# 28Pins_Schematic.net
KiCad netlist of a schematic drawn in Altium Designer
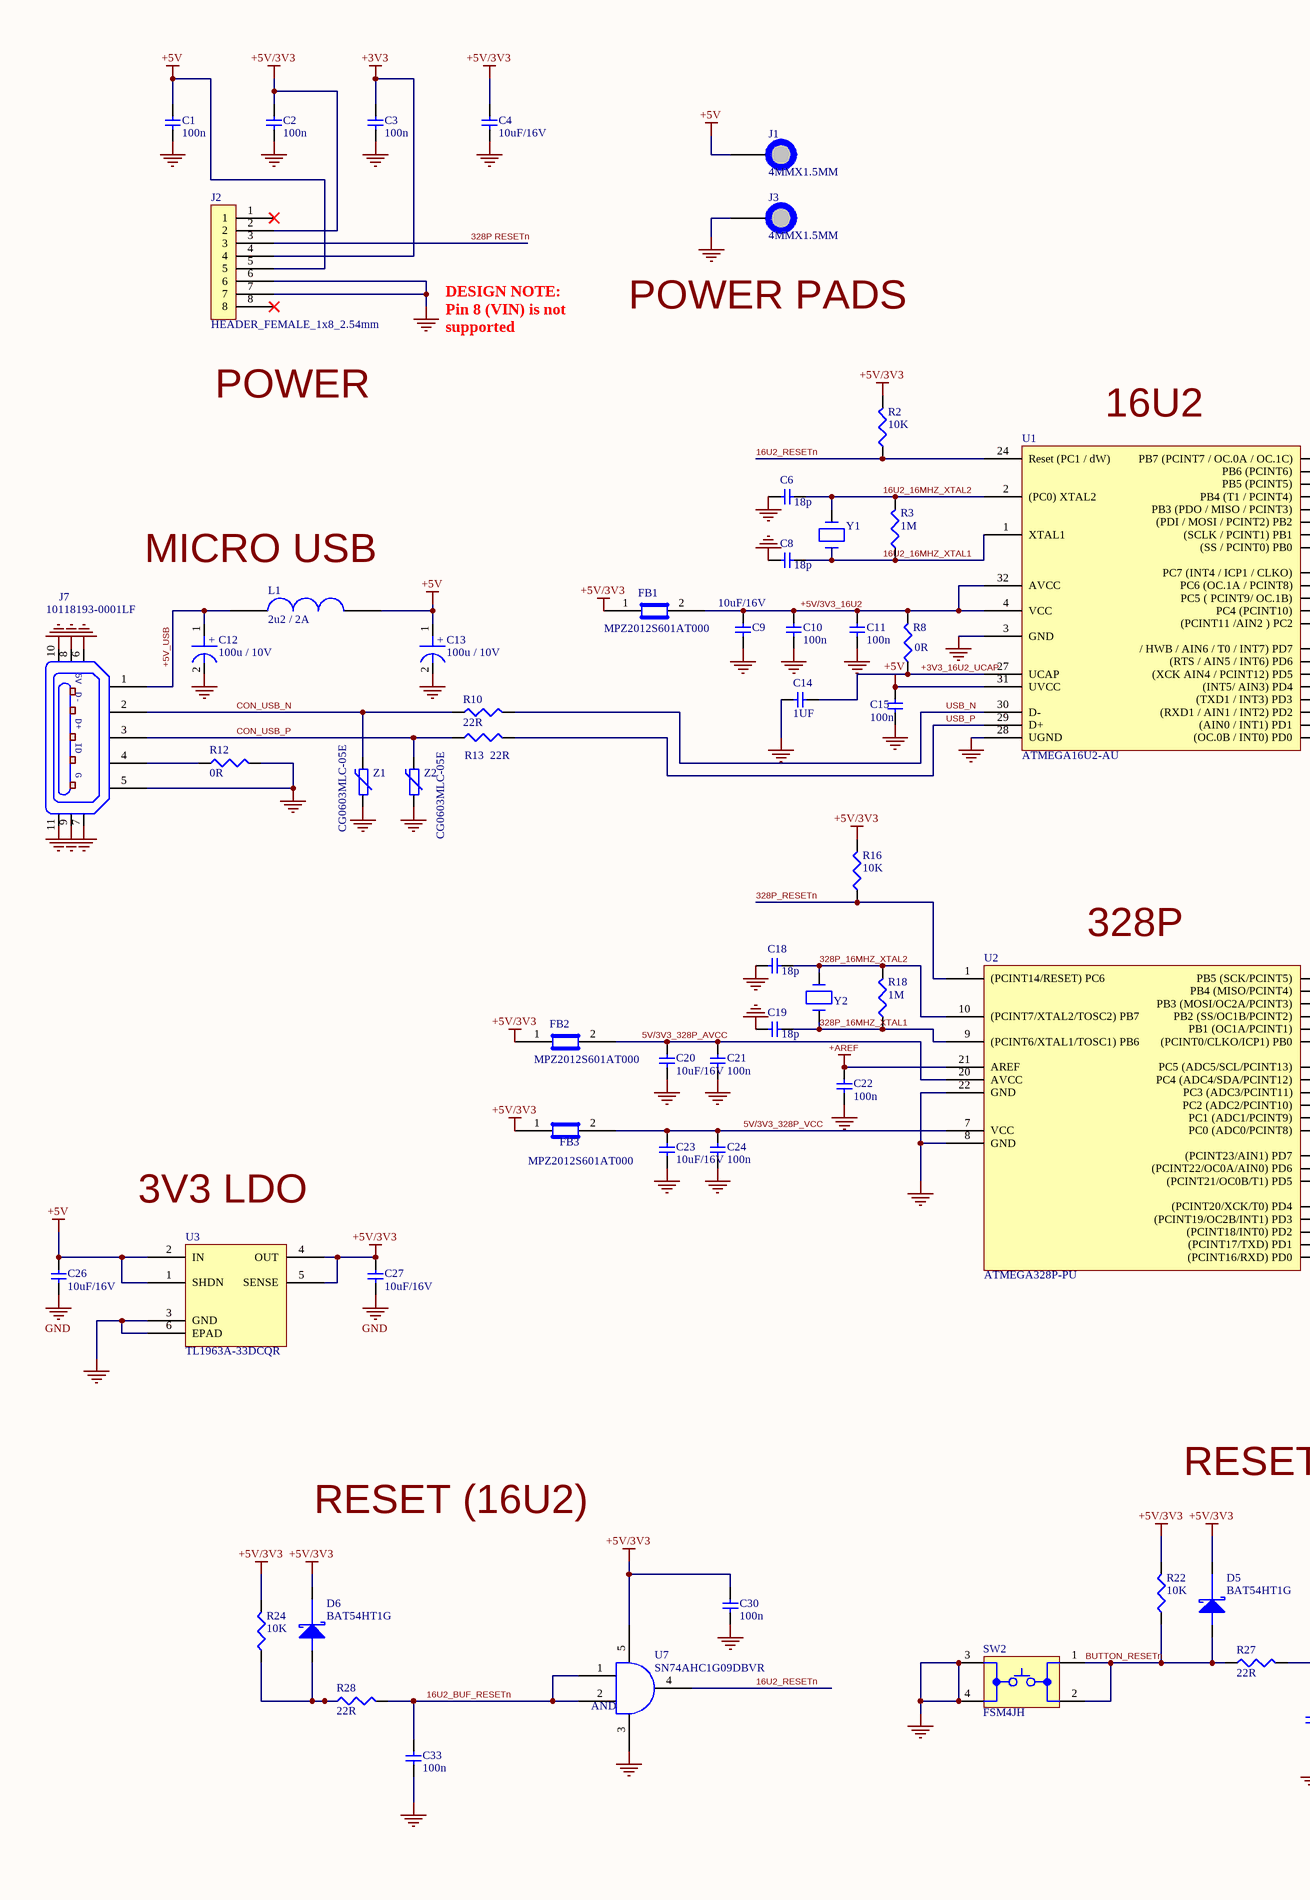
[diagram p0: 28Pins_Schematic.SchDoc, left]
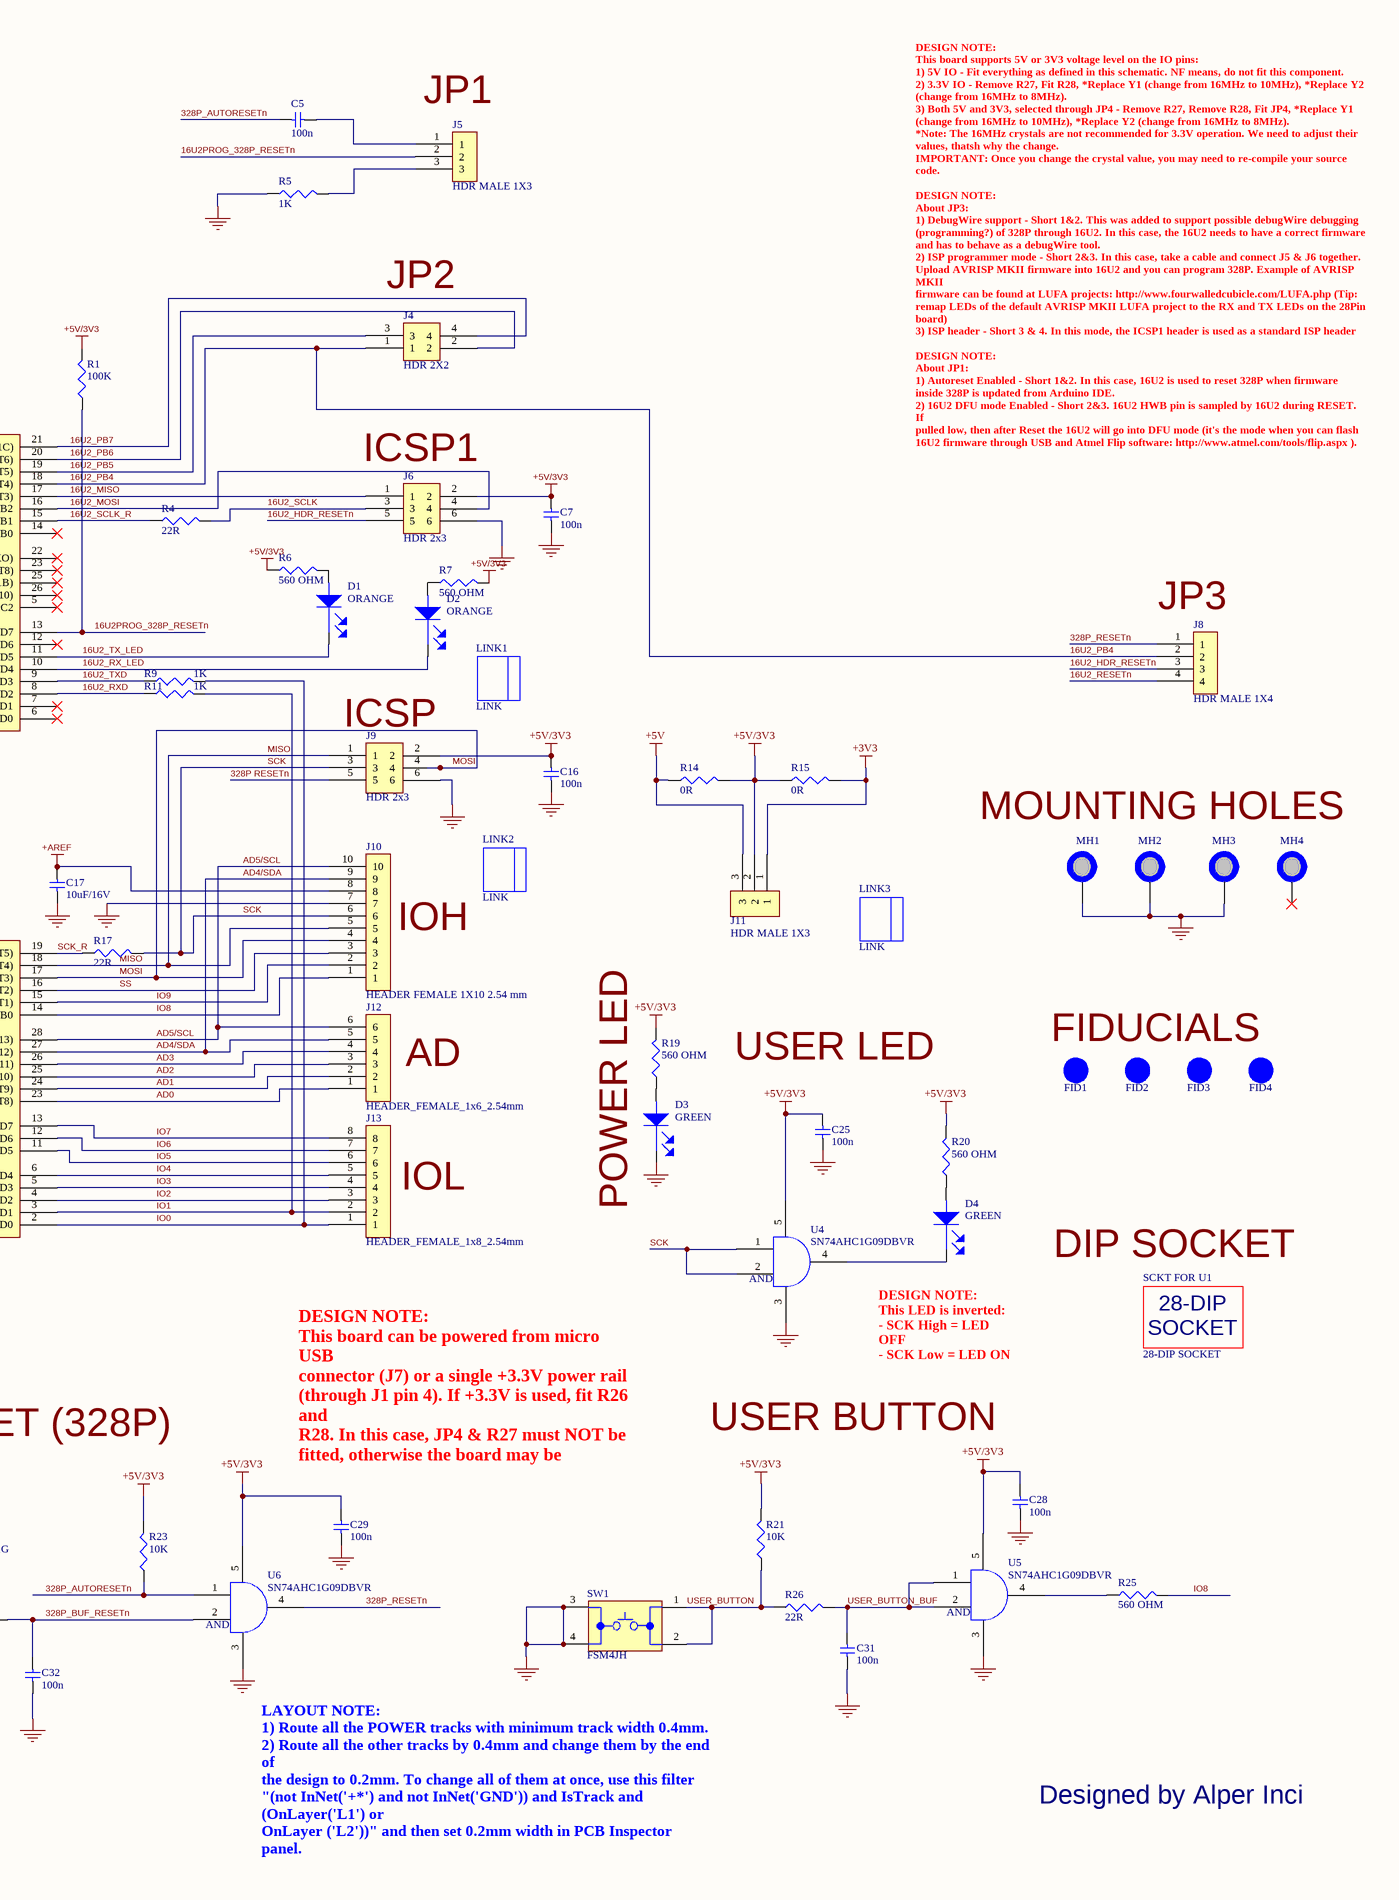
[diagram p1: 28Pins_Schematic.SchDoc, right]

(export (version "E")
  (design (tool "Eeschema 10.0.6"))
  (components
    (comp (ref "C1")
      (value "100n")
      (footprint "C0805")
      (description "CAP CER 0.1UF 50V X7R 0805")
      (fields
        (field (name "MANUFACTURER") "Mouser Electronics")
        (field (name "MANUFACTURER PART NUMBER") "C2012X7R1H104K085AA")
      )
      (libsource (lib "28_Pins_Project_V1I1") (part "C2012X7R1H104K085AA"))
    )
    (comp (ref "C2")
      (value "100n")
      (footprint "C0805")
      (description "CAP CER 0.1UF 50V X7R 0805")
      (fields
        (field (name "MANUFACTURER") "Mouser Electronics")
        (field (name "MANUFACTURER PART NUMBER") "C2012X7R1H104K085AA")
      )
      (libsource (lib "28_Pins_Project_V1I1") (part "C2012X7R1H104K085AA"))
    )
    (comp (ref "C3")
      (value "100n")
      (footprint "C0805")
      (description "CAP CER 0.1UF 50V X7R 0805")
      (fields
        (field (name "MANUFACTURER") "Mouser Electronics")
        (field (name "MANUFACTURER PART NUMBER") "C2012X7R1H104K085AA")
      )
      (libsource (lib "28_Pins_Project_V1I1") (part "C2012X7R1H104K085AA"))
    )
    (comp (ref "C4")
      (value "10uF/16V")
      (footprint "C0805_v2")
      (description "CAP CER 10UF 16V X5R 0805")
      (fields
        (field (name "MANUFACTURER") "Mouser Electronics")
        (field (name "MANUFACTURER PART NUMBER") "C2012X5R1C106M125AC")
      )
      (libsource (lib "28_Pins_Project_V1I1") (part "C2012X5R1C106M125AC"))
    )
    (comp (ref "C5")
      (value "100n")
      (footprint "C0805")
      (description "CAP CER 0.1UF 50V X7R 0805")
      (fields
        (field (name "MANUFACTURER") "Mouser Electronics")
        (field (name "MANUFACTURER PART NUMBER") "C2012X7R1H104K085AA")
      )
      (libsource (lib "28_Pins_Project_V1I1") (part "C2012X7R1H104K085AA"))
    )
    (comp (ref "C6")
      (value "18p")
      (footprint "C0805")
      (description "CAP CER 18PF 50V NP0 0805")
      (fields
        (field (name "MANUFACTURER") "KEMET")
        (field (name "MANUFACTURER PART NUMBER") "C0805C180J5GACTU")
      )
      (libsource (lib "28_Pins_Project_V1I1") (part "C0805C180J5GACTU"))
    )
    (comp (ref "C7")
      (value "100n")
      (footprint "C0805")
      (description "CAP CER 0.1UF 50V X7R 0805")
      (fields
        (field (name "MANUFACTURER") "Mouser Electronics")
        (field (name "MANUFACTURER PART NUMBER") "C2012X7R1H104K085AA")
      )
      (libsource (lib "28_Pins_Project_V1I1") (part "C2012X7R1H104K085AA"))
    )
    (comp (ref "C8")
      (value "18p")
      (footprint "C0805")
      (description "CAP CER 18PF 50V NP0 0805")
      (fields
        (field (name "MANUFACTURER") "KEMET")
        (field (name "MANUFACTURER PART NUMBER") "C0805C180J5GACTU")
      )
      (libsource (lib "28_Pins_Project_V1I1") (part "C0805C180J5GACTU"))
    )
    (comp (ref "C9")
      (value "10uF/16V")
      (footprint "C0805_v2")
      (description "CAP CER 10UF 16V X5R 0805")
      (fields
        (field (name "MANUFACTURER") "Mouser Electronics")
        (field (name "MANUFACTURER PART NUMBER") "C2012X5R1C106M125AC")
      )
      (libsource (lib "28_Pins_Project_V1I1") (part "C2012X5R1C106M125AC"))
    )
    (comp (ref "C10")
      (value "100n")
      (footprint "C0805")
      (description "CAP CER 0.1UF 50V X7R 0805")
      (fields
        (field (name "MANUFACTURER") "Mouser Electronics")
        (field (name "MANUFACTURER PART NUMBER") "C2012X7R1H104K085AA")
      )
      (libsource (lib "28_Pins_Project_V1I1") (part "C2012X7R1H104K085AA"))
    )
    (comp (ref "C11")
      (value "100n")
      (footprint "C0805")
      (description "CAP CER 0.1UF 50V X7R 0805")
      (fields
        (field (name "MANUFACTURER") "Mouser Electronics")
        (field (name "MANUFACTURER PART NUMBER") "C2012X7R1H104K085AA")
      )
      (libsource (lib "28_Pins_Project_V1I1") (part "C2012X7R1H104K085AA"))
    )
    (comp (ref "C12")
      (value "100u / 10V")
      (footprint "C_ALU_C_SIZE")
      (description "CAP ALUM 100UF 20% 10V SMD")
      (fields
        (field (name "MANUFACTURER") "Panasonic")
        (field (name "MANUFACTURER PART NUMBER") "EEE-1AA101WR")
      )
      (libsource (lib "28_Pins_Project_V1I1") (part "EEE-1AA101WR"))
    )
    (comp (ref "C13")
      (value "100u / 10V")
      (footprint "C_ALU_C_SIZE")
      (description "CAP ALUM 100UF 20% 10V SMD")
      (fields
        (field (name "MANUFACTURER") "Panasonic")
        (field (name "MANUFACTURER PART NUMBER") "EEE-1AA101WR")
      )
      (libsource (lib "28_Pins_Project_V1I1") (part "EEE-1AA101WR"))
    )
    (comp (ref "C14")
      (value "1UF")
      (footprint "C0805")
      (description "CAP CER 10UF 16V X5R 0805")
      (fields
        (field (name "MANUFACTURER") "Mouser Electronics")
        (field (name "MANUFACTURER PART NUMBER") "C2012X5R1E105K125AA")
      )
      (libsource (lib "28_Pins_Project_V1I1") (part "C2012X5R1E105K125AA"))
    )
    (comp (ref "C15")
      (value "100n")
      (footprint "C0805")
      (description "CAP CER 0.1UF 50V X7R 0805")
      (fields
        (field (name "MANUFACTURER") "Mouser Electronics")
        (field (name "MANUFACTURER PART NUMBER") "C2012X7R1H104K085AA")
      )
      (libsource (lib "28_Pins_Project_V1I1") (part "C2012X7R1H104K085AA"))
    )
    (comp (ref "C16")
      (value "100n")
      (footprint "C0805")
      (description "CAP CER 0.1UF 50V X7R 0805")
      (fields
        (field (name "MANUFACTURER") "Mouser Electronics")
        (field (name "MANUFACTURER PART NUMBER") "C2012X7R1H104K085AA")
      )
      (libsource (lib "28_Pins_Project_V1I1") (part "C2012X7R1H104K085AA"))
    )
    (comp (ref "C17")
      (value "10uF/16V")
      (footprint "C0805_v2")
      (description "CAP CER 10UF 16V X5R 0805")
      (fields
        (field (name "MANUFACTURER") "Mouser Electronics")
        (field (name "MANUFACTURER PART NUMBER") "C2012X5R1C106M125AC")
      )
      (libsource (lib "28_Pins_Project_V1I1") (part "C2012X5R1C106M125AC"))
    )
    (comp (ref "C18")
      (value "18p")
      (footprint "C0805")
      (description "CAP CER 18PF 50V NP0 0805")
      (fields
        (field (name "MANUFACTURER") "KEMET")
        (field (name "MANUFACTURER PART NUMBER") "C0805C180J5GACTU")
      )
      (libsource (lib "28_Pins_Project_V1I1") (part "C0805C180J5GACTU"))
    )
    (comp (ref "C19")
      (value "18p")
      (footprint "C0805")
      (description "CAP CER 18PF 50V NP0 0805")
      (fields
        (field (name "MANUFACTURER") "KEMET")
        (field (name "MANUFACTURER PART NUMBER") "C0805C180J5GACTU")
      )
      (libsource (lib "28_Pins_Project_V1I1") (part "C0805C180J5GACTU"))
    )
    (comp (ref "C20")
      (value "10uF/16V")
      (footprint "C0805_v2")
      (description "CAP CER 10UF 16V X5R 0805")
      (fields
        (field (name "MANUFACTURER") "Mouser Electronics")
        (field (name "MANUFACTURER PART NUMBER") "C2012X5R1C106M125AC")
      )
      (libsource (lib "28_Pins_Project_V1I1") (part "C2012X5R1C106M125AC"))
    )
    (comp (ref "C21")
      (value "100n")
      (footprint "C0805")
      (description "CAP CER 0.1UF 50V X7R 0805")
      (fields
        (field (name "MANUFACTURER") "Mouser Electronics")
        (field (name "MANUFACTURER PART NUMBER") "C2012X7R1H104K085AA")
      )
      (libsource (lib "28_Pins_Project_V1I1") (part "C2012X7R1H104K085AA"))
    )
    (comp (ref "C22")
      (value "100n")
      (footprint "C0805")
      (description "CAP CER 0.1UF 50V X7R 0805")
      (fields
        (field (name "MANUFACTURER") "Mouser Electronics")
        (field (name "MANUFACTURER PART NUMBER") "C2012X7R1H104K085AA")
      )
      (libsource (lib "28_Pins_Project_V1I1") (part "C2012X7R1H104K085AA"))
    )
    (comp (ref "C23")
      (value "10uF/16V")
      (footprint "C0805_v2")
      (description "CAP CER 10UF 16V X5R 0805")
      (fields
        (field (name "MANUFACTURER") "Mouser Electronics")
        (field (name "MANUFACTURER PART NUMBER") "C2012X5R1C106M125AC")
      )
      (libsource (lib "28_Pins_Project_V1I1") (part "C2012X5R1C106M125AC"))
    )
    (comp (ref "C24")
      (value "100n")
      (footprint "C0805")
      (description "CAP CER 0.1UF 50V X7R 0805")
      (fields
        (field (name "MANUFACTURER") "Mouser Electronics")
        (field (name "MANUFACTURER PART NUMBER") "C2012X7R1H104K085AA")
      )
      (libsource (lib "28_Pins_Project_V1I1") (part "C2012X7R1H104K085AA"))
    )
    (comp (ref "C25")
      (value "100n")
      (footprint "C0805")
      (description "CAP CER 0.1UF 50V X7R 0805")
      (fields
        (field (name "MANUFACTURER") "Mouser Electronics")
        (field (name "MANUFACTURER PART NUMBER") "C2012X7R1H104K085AA")
      )
      (libsource (lib "28_Pins_Project_V1I1") (part "C2012X7R1H104K085AA"))
    )
    (comp (ref "C26")
      (value "10uF/16V")
      (footprint "C0805_v2")
      (description "CAP CER 10UF 16V X5R 0805")
      (fields
        (field (name "MANUFACTURER") "Mouser Electronics")
        (field (name "MANUFACTURER PART NUMBER") "C2012X5R1C106M125AC")
      )
      (libsource (lib "28_Pins_Project_V1I1") (part "C2012X5R1C106M125AC"))
    )
    (comp (ref "C27")
      (value "10uF/16V")
      (footprint "C0805_v2")
      (description "CAP CER 10UF 16V X5R 0805")
      (fields
        (field (name "MANUFACTURER") "Mouser Electronics")
        (field (name "MANUFACTURER PART NUMBER") "C2012X5R1C106M125AC")
      )
      (libsource (lib "28_Pins_Project_V1I1") (part "C2012X5R1C106M125AC"))
    )
    (comp (ref "C28")
      (value "100n")
      (footprint "C0805")
      (description "CAP CER 0.1UF 50V X7R 0805")
      (fields
        (field (name "MANUFACTURER") "Mouser Electronics")
        (field (name "MANUFACTURER PART NUMBER") "C2012X7R1H104K085AA")
      )
      (libsource (lib "28_Pins_Project_V1I1") (part "C2012X7R1H104K085AA"))
    )
    (comp (ref "C29")
      (value "100n")
      (footprint "C0805")
      (description "CAP CER 0.1UF 50V X7R 0805")
      (fields
        (field (name "MANUFACTURER") "Mouser Electronics")
        (field (name "MANUFACTURER PART NUMBER") "C2012X7R1H104K085AA")
      )
      (libsource (lib "28_Pins_Project_V1I1") (part "C2012X7R1H104K085AA"))
    )
    (comp (ref "C30")
      (value "100n")
      (footprint "C0805")
      (description "CAP CER 0.1UF 50V X7R 0805")
      (fields
        (field (name "MANUFACTURER") "Mouser Electronics")
        (field (name "MANUFACTURER PART NUMBER") "C2012X7R1H104K085AA")
      )
      (libsource (lib "28_Pins_Project_V1I1") (part "C2012X7R1H104K085AA"))
    )
    (comp (ref "C31")
      (value "100n")
      (footprint "C0805")
      (description "CAP CER 0.1UF 50V X7R 0805")
      (fields
        (field (name "MANUFACTURER") "Mouser Electronics")
        (field (name "MANUFACTURER PART NUMBER") "C2012X7R1H104K085AA")
      )
      (libsource (lib "28_Pins_Project_V1I1") (part "C2012X7R1H104K085AA"))
    )
    (comp (ref "C32")
      (value "100n")
      (footprint "C0805")
      (description "CAP CER 0.1UF 50V X7R 0805")
      (fields
        (field (name "MANUFACTURER") "Mouser Electronics")
        (field (name "MANUFACTURER PART NUMBER") "C2012X7R1H104K085AA")
      )
      (libsource (lib "28_Pins_Project_V1I1") (part "C2012X7R1H104K085AA"))
    )
    (comp (ref "C33")
      (value "100n")
      (footprint "C0805")
      (description "CAP CER 0.1UF 50V X7R 0805")
      (fields
        (field (name "MANUFACTURER") "Mouser Electronics")
        (field (name "MANUFACTURER PART NUMBER") "C2012X7R1H104K085AA")
      )
      (libsource (lib "28_Pins_Project_V1I1") (part "C2012X7R1H104K085AA"))
    )
    (comp (ref "D1")
      (value "ORANGE")
      (footprint "LED_0603")
      (description "LED ORANGE DIFFUSED 0603 SMD")
      (fields
        (field (name "MANUFACTURER") "Carling Technologies")
        (field (name "MANUFACTURER PART NUMBER") "LO L29K-H2K1-24-Z")
      )
      (libsource (lib "28_Pins_Project_V1I1") (part "LO L29K-H2K1-24-Z"))
    )
    (comp (ref "D2")
      (value "ORANGE")
      (footprint "LED_0603")
      (description "LED ORANGE DIFFUSED 0603 SMD")
      (fields
        (field (name "MANUFACTURER") "Carling Technologies")
        (field (name "MANUFACTURER PART NUMBER") "LO L29K-H2K1-24-Z")
      )
      (libsource (lib "28_Pins_Project_V1I1") (part "LO L29K-H2K1-24-Z"))
    )
    (comp (ref "D3")
      (value "GREEN")
      (footprint "LED_0603")
      (description "LED GREEN DIFFUSED 0603 SMD")
      (fields
        (field (name "MANUFACTURER") "Osram Opto Semiconductors")
        (field (name "MANUFACTURER PART NUMBER") "LG L29K-G2J1-24-Z")
      )
      (libsource (lib "28_Pins_Project_V1I1") (part "LG L29K-G2J1-24-Z"))
    )
    (comp (ref "D4")
      (value "GREEN")
      (footprint "LED_0603")
      (description "LED GREEN DIFFUSED 0603 SMD")
      (fields
        (field (name "MANUFACTURER") "Osram Opto Semiconductors")
        (field (name "MANUFACTURER PART NUMBER") "LG L29K-G2J1-24-Z")
      )
      (libsource (lib "28_Pins_Project_V1I1") (part "LG L29K-G2J1-24-Z"))
    )
    (comp (ref "D5")
      (value "BAT54HT1G")
      (footprint "SOD323")
      (description "DIODE SCHOTTKY 30V 200MA SOD323")
      (fields (field (name "MANUFACTURER") "ON Semiconductor"))
      (libsource (lib "28_Pins_Project_V1I1") (part "BAT54HT1G"))
    )
    (comp (ref "D6")
      (value "BAT54HT1G")
      (footprint "SOD323")
      (description "DIODE SCHOTTKY 30V 200MA SOD323")
      (fields (field (name "MANUFACTURER") "ON Semiconductor"))
      (libsource (lib "28_Pins_Project_V1I1") (part "BAT54HT1G"))
    )
    (comp (ref "FB1")
      (value "MPZ2012S601AT000")
      (footprint "C0805")
      (description "FERRITE CHIP BEAD  600 OHM SMD")
      (fields (field (name "MANUFACTURER") "Mouser Electronics"))
      (libsource (lib "28_Pins_Project_V1I1") (part "MPZ2012S601AT000"))
    )
    (comp (ref "FB2")
      (value "MPZ2012S601AT000")
      (footprint "C0805")
      (description "FERRITE CHIP BEAD  600 OHM SMD")
      (fields (field (name "MANUFACTURER") "Mouser Electronics"))
      (libsource (lib "28_Pins_Project_V1I1") (part "MPZ2012S601AT000"))
    )
    (comp (ref "FB3")
      (value "MPZ2012S601AT000")
      (footprint "C0805")
      (description "FERRITE CHIP BEAD  600 OHM SMD")
      (fields (field (name "MANUFACTURER") "Mouser Electronics"))
      (libsource (lib "28_Pins_Project_V1I1") (part "MPZ2012S601AT000"))
    )
    (comp (ref "FID1")
      (value "FID 1MM")
      (footprint "FID_40X120D")
      (description "FIDUCIAL 40MIL DIAMETER,120 MIL MASK")
      (libsource (lib "28_Pins_Project_V1I1") (part "FID_1MMC"))
    )
    (comp (ref "FID2")
      (value "FID 1MM")
      (footprint "FID_40X120D")
      (description "FIDUCIAL 40MIL DIAMETER,120 MIL MASK")
      (libsource (lib "28_Pins_Project_V1I1") (part "FID_1MMC"))
    )
    (comp (ref "FID3")
      (value "FID 1MM")
      (footprint "FID_40X120D")
      (description "FIDUCIAL 40MIL DIAMETER,120 MIL MASK")
      (libsource (lib "28_Pins_Project_V1I1") (part "FID_1MMC"))
    )
    (comp (ref "FID4")
      (value "FID 1MM")
      (footprint "FID_40X120D")
      (description "FIDUCIAL 40MIL DIAMETER,120 MIL MASK")
      (libsource (lib "28_Pins_Project_V1I1") (part "FID_1MMC"))
    )
    (comp (ref "J1")
      (value "4MMX1.5MM")
      (footprint "PAD_WTIH_HOLE_4MMX1.5MM")
      (description "PAD WITH A HOLE")
      (libsource (lib "28_Pins_Project_V1I1") (part "PAD_WITH_HOLE_4MMX1.5MM"))
    )
    (comp (ref "J2")
      (value "HEADER_FEMALE_1x8_2.54mm")
      (footprint "HEADER_FEMALE_1X8_2.54mm")
      (description "HARWIN 2.54mm 8 Way 1 Row Straight PCBSocket Through Hole Socket Strip")
      (fields
        (field (name "MANUFACTURER") "Mouser Electronics")
        (field (name "MANUFACTURER PART NUMBER") "M20-7820842")
      )
      (libsource (lib "28_Pins_Project_V1I1") (part "M20-7820842"))
    )
    (comp (ref "J3")
      (value "4MMX1.5MM")
      (footprint "PAD_WTIH_HOLE_4MMX1.5MM")
      (description "PAD WITH A HOLE")
      (libsource (lib "28_Pins_Project_V1I1") (part "PAD_WITH_HOLE_4MMX1.5MM"))
    )
    (comp (ref "J4")
      (value "HDR 2X2")
      (footprint "HDR_2X2_2.54mm")
      (description "CONN HEADER 4POS .100 STR 30AU")
      (fields
        (field (name "MANUFACTURER") "Mouser Electronics")
        (field (name "MANUFACTURER PART NUMBER") "68602-204HLF")
      )
      (libsource (lib "28_Pins_Project_V1I1") (part "68602-204HLF"))
    )
    (comp (ref "J5")
      (value "HDR MALE 1X3")
      (footprint "HEADER_MALE_1X3_2.54mm")
      (description "HDR MALE 1X3 2.54 MM")
      (fields
        (field (name "MANUFACTURER") "Amphenol ICC")
        (field (name "MANUFACTURER PART NUMBER") "68000-103HLF")
      )
      (libsource (lib "") (part "68000-103HLF_1"))
    )
    (comp (ref "J6")
      (value "HDR 2x3")
      (footprint "HDR_2X3_2.54mm")
      (description "CONN HEADER 6POS .100 STR 30AU")
      (fields
        (field (name "MANUFACTURER") "Amphenol ICC")
        (field (name "MANUFACTURER PART NUMBER") "67997-106HLF")
      )
      (libsource (lib "28_Pins_Project_V1I1") (part "67997-106HLF"))
    )
    (comp (ref "J7")
      (value "10118193-0001LF")
      (footprint "10118193")
      (description "CONN USB MICRO B RECPT SMT R/A")
      (fields (field (name "MANUFACTURER") "Amphenol ICC"))
      (libsource (lib "28_Pins_Project_V1I1") (part "10118193-0001LF"))
    )
    (comp (ref "J8")
      (value "HDR MALE 1X4")
      (footprint "HEADER_MALE_1X4_2.54mm")
      (description "HDR MALE 1X4 2.54MM")
      (fields
        (field (name "MANUFACTURER") "Amphenol ICC")
        (field (name "MANUFACTURER PART NUMBER") "68001-204HLF")
      )
      (libsource (lib "28_Pins_Project_V1I1") (part "68001-204HLF"))
    )
    (comp (ref "J9")
      (value "HDR 2x3")
      (footprint "HDR_2X3_2.54mm")
      (description "CONN HEADER 6POS .100 STR 30AU")
      (fields
        (field (name "MANUFACTURER") "Amphenol ICC")
        (field (name "MANUFACTURER PART NUMBER") "67997-106HLF")
      )
      (libsource (lib "28_Pins_Project_V1I1") (part "67997-106HLF"))
    )
    (comp (ref "J10")
      (value "HEADER FEMALE 1X10 2.54 mm")
      (footprint "HEADER_FEMALE_1X10_2.54mm")
      (description "HARWIN 2.54mm 10 Way 1 Row Straight PCBSocket Through Hole Socket Strip")
      (fields (field (name "MANUFACTURER PART NUMBER") "M20-7821046"))
      (libsource (lib "28_Pins_Project_V1I1") (part "M20-7821046"))
    )
    (comp (ref "J11")
      (value "HDR MALE 1X3")
      (footprint "HEADER_MALE_1X3_2.54mm")
      (description "HDR MALE 1X3 2.54 MM")
      (fields
        (field (name "MANUFACTURER") "Amphenol ICC")
        (field (name "MANUFACTURER PART NUMBER") "68000-103HLF")
      )
      (libsource (lib "28_Pins_Project_V1I1") (part "68000-103HLF"))
    )
    (comp (ref "J12")
      (value "HEADER_FEMALE_1x6_2.54mm")
      (footprint "HEADER_FEMALE_1X6_2.54mm")
      (description "HARWIN 2.54mm 6 Way 1 Row Straight PCBSocket Through Hole Socket Strip")
      (fields
        (field (name "MANUFACTURER") "Mouser Electronics")
        (field (name "MANUFACTURER PART NUMBER") "M20-7820646")
      )
      (libsource (lib "28_Pins_Project_V1I1") (part "M20-7820646"))
    )
    (comp (ref "J13")
      (value "HEADER_FEMALE_1x8_2.54mm")
      (footprint "HEADER_FEMALE_1X8_2.54mm")
      (description "HARWIN 2.54mm 8 Way 1 Row Straight PCBSocket Through Hole Socket Strip")
      (fields
        (field (name "MANUFACTURER") "Mouser Electronics")
        (field (name "MANUFACTURER PART NUMBER") "M20-7820842")
      )
      (libsource (lib "") (part "M20-7820842_1"))
    )
    (comp (ref "L1")
      (value "2u2 / 2A")
      (footprint "C1210_IND")
      (description "FIXED IND 2.2UH 2A 80MOHM SMD")
      (fields
        (field (name "MANUFACTURER") "Mouser Electronics")
        (field (name "MANUFACTURER PART NUMBER") "L1210R2R2MDWIT")
      )
      (libsource (lib "28_Pins_Project_V1I1") (part "L1210R2R2MDWIT"))
    )
    (comp (ref "LINK1")
      (value "LINK")
      (description "QPC02SXGN-RC")
      (fields (field (name "MANUFACTURER") "Mouser Electronics"))
      (libsource (lib "28_Pins_Project_V1I1") (part "QPC02SXGN-RC"))
    )
    (comp (ref "LINK2")
      (value "LINK")
      (description "QPC02SXGN-RC")
      (fields (field (name "MANUFACTURER") "Mouser Electronics"))
      (libsource (lib "28_Pins_Project_V1I1") (part "QPC02SXGN-RC"))
    )
    (comp (ref "LINK3")
      (value "LINK")
      (description "QPC02SXGN-RC")
      (fields (field (name "MANUFACTURER") "Mouser Electronics"))
      (libsource (lib "28_Pins_Project_V1I1") (part "QPC02SXGN-RC"))
    )
    (comp (ref "MH1")
      (value "MH_7.4MMC_3.2MMD")
      (footprint "MH_7.4MMC_3.2MMD")
      (description "MOUNTING HOLE 7.4MM DIAMETER,3.2MM DRILL")
      (libsource (lib "28_Pins_Project_V1I1") (part "MH_7.4MMC_3.2MMD"))
    )
    (comp (ref "MH2")
      (value "MH_7.4MMC_3.2MMD")
      (footprint "MH_7.4MMC_3.2MMD")
      (description "MOUNTING HOLE 7.4MM DIAMETER,3.2MM DRILL")
      (libsource (lib "28_Pins_Project_V1I1") (part "MH_7.4MMC_3.2MMD"))
    )
    (comp (ref "MH3")
      (value "MH_7.4MMC_3.2MMD")
      (footprint "MH_7.4MMC_3.2MMD")
      (description "MOUNTING HOLE 7.4MM DIAMETER,3.2MM DRILL")
      (libsource (lib "28_Pins_Project_V1I1") (part "MH_7.4MMC_3.2MMD"))
    )
    (comp (ref "MH4")
      (value "MH_7.4MMNC_3.2MMD")
      (footprint "MH_7.4MMNC_3.2MMD_NON_COPPER_NPTH")
      (description "HOLE 7.4MM DIAMETER (NON COPPER), 3.2MM DRILL NPTH")
      (libsource (lib "28_Pins_Project_V1I1") (part "MH_7.4MMNC_3.2MMD"))
    )
    (comp (ref "R1")
      (value "100K")
      (footprint "R0805")
      (description "RES SMD 100K OHM 1% 1/8W 0805")
      (fields
        (field (name "MANUFACTURER") "Mouser Electronics")
        (field (name "MANUFACTURER PART NUMBER") "RC0805FR-07100KL")
      )
      (libsource (lib "28_Pins_Project_V1I1") (part "RC0805FR-07100KL"))
    )
    (comp (ref "R2")
      (value "10K")
      (footprint "R0805")
      (description "RES SMD 10K OHM 1/8 W 0805")
      (fields
        (field (name "MANUFACTURER") "Mouser Electronics")
        (field (name "MANUFACTURER PART NUMBER") "RC0805FR-0710KL")
      )
      (libsource (lib "28_Pins_Project_V1I1") (part "RC0805FR-0710KL"))
    )
    (comp (ref "R3")
      (value "1M")
      (footprint "R0805")
      (description "RES SMD 1M OHM 1% 1/8W 0805")
      (fields
        (field (name "MANUFACTURER") "Mouser Electronics")
        (field (name "MANUFACTURER PART NUMBER") "RC0805FR-071ML")
      )
      (libsource (lib "28_Pins_Project_V1I1") (part "RC0805FR-071ML"))
    )
    (comp (ref "R4")
      (value "22R")
      (footprint "R0805")
      (description "RES SMD 22 OHM 1% 1/8W 0805")
      (fields
        (field (name "MANUFACTURER") "Mouser Electronics")
        (field (name "MANUFACTURER PART NUMBER") "RC0805FR-0722RL")
      )
      (libsource (lib "28_Pins_Project_V1I1") (part "RC0805FR-0722RL"))
    )
    (comp (ref "R5")
      (value "1K")
      (footprint "R0805")
      (description "RES SMD 1K OHM 1% 1/8W 0805")
      (fields
        (field (name "MANUFACTURER") "Mouser Electronics")
        (field (name "MANUFACTURER PART NUMBER") "RC0805FR-071KL")
      )
      (libsource (lib "28_Pins_Project_V1I1") (part "RC0805FR-071KL"))
    )
    (comp (ref "R6")
      (value "560 OHM")
      (footprint "R0805")
      (description "RES SMD 560 OHM 1% 1/8W 0805")
      (fields
        (field (name "MANUFACTURER") "Mouser Electronics")
        (field (name "MANUFACTURER PART NUMBER") "RC0805FR-07560RL")
      )
      (libsource (lib "28_Pins_Project_V1I1") (part "RC0805FR-07560RL"))
    )
    (comp (ref "R7")
      (value "560 OHM")
      (footprint "R0805")
      (description "RES SMD 560 OHM 1% 1/8W 0805")
      (fields
        (field (name "MANUFACTURER") "Mouser Electronics")
        (field (name "MANUFACTURER PART NUMBER") "RC0805FR-07560RL")
      )
      (libsource (lib "28_Pins_Project_V1I1") (part "RC0805FR-07560RL"))
    )
    (comp (ref "R8")
      (value "0R")
      (footprint "R0805")
      (description "RES SMD 0 OHM 1% 1/8W 0805")
      (fields
        (field (name "MANUFACTURER") "Mouser Electronics")
        (field (name "MANUFACTURER PART NUMBER") "RC0805JR-070RL")
      )
      (libsource (lib "28_Pins_Project_V1I1") (part "RC0805JR-070RL"))
    )
    (comp (ref "R9")
      (value "1K")
      (footprint "R0805")
      (description "RES SMD 1K OHM 1% 1/8W 0805")
      (fields
        (field (name "MANUFACTURER") "Mouser Electronics")
        (field (name "MANUFACTURER PART NUMBER") "RC0805FR-071KL")
      )
      (libsource (lib "28_Pins_Project_V1I1") (part "RC0805FR-071KL"))
    )
    (comp (ref "R10")
      (value "22R")
      (footprint "R0805")
      (description "RES SMD 22 OHM 1% 1/8W 0805")
      (fields
        (field (name "MANUFACTURER") "Mouser Electronics")
        (field (name "MANUFACTURER PART NUMBER") "RC0805FR-0722RL")
      )
      (libsource (lib "28_Pins_Project_V1I1") (part "RC0805FR-0722RL"))
    )
    (comp (ref "R11")
      (value "1K")
      (footprint "R0805")
      (description "RES SMD 1K OHM 1% 1/8W 0805")
      (fields
        (field (name "MANUFACTURER") "Mouser Electronics")
        (field (name "MANUFACTURER PART NUMBER") "RC0805FR-071KL")
      )
      (libsource (lib "28_Pins_Project_V1I1") (part "RC0805FR-071KL"))
    )
    (comp (ref "R12")
      (value "0R")
      (footprint "R0805")
      (description "RES SMD 0 OHM 1% 1/8W 0805")
      (fields
        (field (name "MANUFACTURER") "Mouser Electronics")
        (field (name "MANUFACTURER PART NUMBER") "RC0805JR-070RL")
      )
      (libsource (lib "28_Pins_Project_V1I1") (part "RC0805JR-070RL"))
    )
    (comp (ref "R13")
      (value "22R")
      (footprint "R0805")
      (description "RES SMD 22 OHM 1% 1/8W 0805")
      (fields
        (field (name "MANUFACTURER") "Mouser Electronics")
        (field (name "MANUFACTURER PART NUMBER") "RC0805FR-0722RL")
      )
      (libsource (lib "28_Pins_Project_V1I1") (part "RC0805FR-0722RL"))
    )
    (comp (ref "R14")
      (value "0R")
      (footprint "R0805")
      (description "RES SMD 0 OHM 1% 1/8W 0805")
      (fields
        (field (name "MANUFACTURER") "Mouser Electronics")
        (field (name "MANUFACTURER PART NUMBER") "RC0805JR-070RL")
      )
      (libsource (lib "") (part "RC0805JR-070RL_1"))
    )
    (comp (ref "R15")
      (value "0R")
      (footprint "R0805")
      (description "RES SMD 0 OHM 1% 1/8W 0805")
      (fields
        (field (name "MANUFACTURER") "Mouser Electronics")
        (field (name "MANUFACTURER PART NUMBER") "RC0805JR-070RL")
      )
      (libsource (lib "") (part "RC0805JR-070RL_1"))
    )
    (comp (ref "R16")
      (value "10K")
      (footprint "R0805")
      (description "RES SMD 10K OHM 1/8 W 0805")
      (fields
        (field (name "MANUFACTURER") "Mouser Electronics")
        (field (name "MANUFACTURER PART NUMBER") "RC0805FR-0710KL")
      )
      (libsource (lib "28_Pins_Project_V1I1") (part "RC0805FR-0710KL"))
    )
    (comp (ref "R17")
      (value "22R")
      (footprint "R0805")
      (description "RES SMD 22 OHM 1% 1/8W 0805")
      (fields
        (field (name "MANUFACTURER") "Mouser Electronics")
        (field (name "MANUFACTURER PART NUMBER") "RC0805FR-0722RL")
      )
      (libsource (lib "28_Pins_Project_V1I1") (part "RC0805FR-0722RL"))
    )
    (comp (ref "R18")
      (value "1M")
      (footprint "R0805")
      (description "RES SMD 1M OHM 1% 1/8W 0805")
      (fields
        (field (name "MANUFACTURER") "Mouser Electronics")
        (field (name "MANUFACTURER PART NUMBER") "RC0805FR-071ML")
      )
      (libsource (lib "28_Pins_Project_V1I1") (part "RC0805FR-071ML"))
    )
    (comp (ref "R19")
      (value "560 OHM")
      (footprint "R0805")
      (description "RES SMD 560 OHM 1% 1/8W 0805")
      (fields
        (field (name "MANUFACTURER") "Mouser Electronics")
        (field (name "MANUFACTURER PART NUMBER") "RC0805FR-07560RL")
      )
      (libsource (lib "28_Pins_Project_V1I1") (part "RC0805FR-07560RL"))
    )
    (comp (ref "R20")
      (value "560 OHM")
      (footprint "R0805")
      (description "RES SMD 560 OHM 1% 1/8W 0805")
      (fields
        (field (name "MANUFACTURER") "Mouser Electronics")
        (field (name "MANUFACTURER PART NUMBER") "RC0805FR-07560RL")
      )
      (libsource (lib "28_Pins_Project_V1I1") (part "RC0805FR-07560RL"))
    )
    (comp (ref "R21")
      (value "10K")
      (footprint "R0805")
      (description "RES SMD 10K OHM 1/8 W 0805")
      (fields
        (field (name "MANUFACTURER") "Mouser Electronics")
        (field (name "MANUFACTURER PART NUMBER") "RC0805FR-0710KL")
      )
      (libsource (lib "28_Pins_Project_V1I1") (part "RC0805FR-0710KL"))
    )
    (comp (ref "R22")
      (value "10K")
      (footprint "R0805")
      (description "RES SMD 10K OHM 1/8 W 0805")
      (fields
        (field (name "MANUFACTURER") "Mouser Electronics")
        (field (name "MANUFACTURER PART NUMBER") "RC0805FR-0710KL")
      )
      (libsource (lib "28_Pins_Project_V1I1") (part "RC0805FR-0710KL"))
    )
    (comp (ref "R23")
      (value "10K")
      (footprint "R0805")
      (description "RES SMD 10K OHM 1/8 W 0805")
      (fields
        (field (name "MANUFACTURER") "Mouser Electronics")
        (field (name "MANUFACTURER PART NUMBER") "RC0805FR-0710KL")
      )
      (libsource (lib "28_Pins_Project_V1I1") (part "RC0805FR-0710KL"))
    )
    (comp (ref "R24")
      (value "10K")
      (footprint "R0805")
      (description "RES SMD 10K OHM 1/8 W 0805")
      (fields
        (field (name "MANUFACTURER") "Mouser Electronics")
        (field (name "MANUFACTURER PART NUMBER") "RC0805FR-0710KL")
      )
      (libsource (lib "28_Pins_Project_V1I1") (part "RC0805FR-0710KL"))
    )
    (comp (ref "R25")
      (value "560 OHM")
      (footprint "R0805")
      (description "RES SMD 560 OHM 1% 1/8W 0805")
      (fields
        (field (name "MANUFACTURER") "Mouser Electronics")
        (field (name "MANUFACTURER PART NUMBER") "RC0805FR-07560RL")
      )
      (libsource (lib "28_Pins_Project_V1I1") (part "RC0805FR-07560RL"))
    )
    (comp (ref "R26")
      (value "22R")
      (footprint "R0805")
      (description "RES SMD 22 OHM 1% 1/8W 0805")
      (fields
        (field (name "MANUFACTURER") "Mouser Electronics")
        (field (name "MANUFACTURER PART NUMBER") "RC0805FR-0722RL")
      )
      (libsource (lib "28_Pins_Project_V1I1") (part "RC0805FR-0722RL"))
    )
    (comp (ref "R27")
      (value "22R")
      (footprint "R0805")
      (description "RES SMD 22 OHM 1% 1/8W 0805")
      (fields
        (field (name "MANUFACTURER") "Mouser Electronics")
        (field (name "MANUFACTURER PART NUMBER") "RC0805FR-0722RL")
      )
      (libsource (lib "28_Pins_Project_V1I1") (part "RC0805FR-0722RL"))
    )
    (comp (ref "R28")
      (value "22R")
      (footprint "R0805")
      (description "RES SMD 22 OHM 1% 1/8W 0805")
      (fields
        (field (name "MANUFACTURER") "Mouser Electronics")
        (field (name "MANUFACTURER PART NUMBER") "RC0805FR-0722RL")
      )
      (libsource (lib "28_Pins_Project_V1I1") (part "RC0805FR-0722RL"))
    )
    (comp (ref "SCKT FOR U1")
      (value "28-DIP SOCKET")
      (footprint "28_DIP_7.62MM_SOCKET")
      (description "CONN IC  DIP SOCKET 28POS TIN")
      (fields (field (name "MANUFACTURER") "3M") (field (name "MANUFACTURER PART NUMBER") "4828-3004-CP"))
      (libsource (lib "28_Pins_Project_V1I1") (part "4828-3004-CP"))
    )
    (comp (ref "SW1")
      (value "FSM4JH")
      (footprint "FSM4JH")
      (description "Alcoswitch, Switch,Pushbutton,Tactile,SPST,50mA,Thru Hole,6mm")
      (fields (field (name "MANUFACTURER") "TE Connectivity"))
      (libsource (lib "28_Pins_Project_V1I1") (part "FSM4JH"))
    )
    (comp (ref "SW2")
      (value "FSM4JH")
      (footprint "FSM4JH")
      (description "Alcoswitch, Switch,Pushbutton,Tactile,SPST,50mA,Thru Hole,6mm")
      (fields (field (name "MANUFACTURER") "TE Connectivity"))
      (libsource (lib "28_Pins_Project_V1I1") (part "FSM4JH"))
    )
    (comp (ref "U1")
      (value "ATMEGA16U2-AU")
      (footprint "TQFP32")
      (fields (field (name "MANUFACTURER") "Mouser Electronics"))
      (libsource (lib "28_Pins_Project_V1I1") (part "ATMEGA16U2-AU"))
    )
    (comp (ref "U2")
      (value "ATMEGA328P-PU")
      (footprint "28_DIP_7.62mm")
      (description "ATMEGA328P-PU; 8 bit Microcontroller AVR 20MHz 1; 32kb Flash; 2kb RAM; I2C SPI 2")
      (fields (field (name "MANUFACTURER") "Microchip Technology Inc."))
      (libsource (lib "28_Pins_Project_V1I1") (part "ATMEGA328P-PU"))
    )
    (comp (ref "U3")
      (value "TL1963A-33DCQR")
      (footprint "DCQ (R-PDSO-G6)")
      (description "IC REG LDO 3.3V 1.5A SOT223-6")
      (fields (field (name "MANUFACTURER") "Mouser Electronics"))
      (libsource (lib "28_Pins_Project_V1I1") (part "TL1963A-33DCQR"))
    )
    (comp (ref "U4")
      (value "SN74AHC1G09DBVR")
      (footprint "DBV_SOT_23_5")
      (description "IC GATE AND 1 CH 2-INP SOT-23-5")
      (fields (field (name "MANUFACTURER") "Mouser Electronics"))
      (libsource (lib "28_Pins_Project_V1I1") (part "SN74AHC1G09DBVR"))
    )
    (comp (ref "U5")
      (value "SN74AHC1G09DBVR")
      (footprint "DBV_SOT_23_5")
      (description "IC GATE AND 1 CH 2-INP SOT-23-5")
      (fields (field (name "MANUFACTURER") "Mouser Electronics"))
      (libsource (lib "28_Pins_Project_V1I1") (part "SN74AHC1G09DBVR"))
    )
    (comp (ref "U6")
      (value "SN74AHC1G09DBVR")
      (footprint "DBV_SOT_23_5")
      (description "IC GATE AND 1 CH 2-INP SOT-23-5")
      (fields (field (name "MANUFACTURER") "Mouser Electronics"))
      (libsource (lib "28_Pins_Project_V1I1") (part "SN74AHC1G09DBVR"))
    )
    (comp (ref "U7")
      (value "SN74AHC1G09DBVR")
      (footprint "DBV_SOT_23_5")
      (description "IC GATE AND 1 CH 2-INP SOT-23-5")
      (fields (field (name "MANUFACTURER") "Mouser Electronics"))
      (libsource (lib "28_Pins_Project_V1I1") (part "SN74AHC1G09DBVR"))
    )
    (comp (ref "Y1")
      (value "ABM7-16.000MHZ-D2Y-T")
      (footprint "ABM_v1_1_BIG")
      (description "Crystal; Ceramic; 16.000MHZ; 18pf; 20ppm @ 25C; 30ppm -40+85C; 6.0 x 3.5 x 1.2mm; T/R")
      (fields (field (name "MANUFACTURER") "Abracon"))
      (libsource (lib "28_Pins_Project_V1I1") (part "ABM7-16.000MHZ-D2Y-T"))
    )
    (comp (ref "Y2")
      (value "ABM7-16.000MHZ-D2Y-T")
      (footprint "ABM_v1_1_BIG")
      (description "Crystal; Ceramic; 16.000MHZ; 18pf; 20ppm @ 25C; 30ppm -40+85C; 6.0 x 3.5 x 1.2mm; T/R")
      (fields (field (name "MANUFACTURER") "Abracon"))
      (libsource (lib "28_Pins_Project_V1I1") (part "ABM7-16.000MHZ-D2Y-T"))
    )
    (comp (ref "Z1")
      (value "CG0603MLC-05E")
      (footprint "R0603")
      (description "VARISTOR 0603")
      (fields (field (name "MANUFACTURER") "Bourns"))
      (libsource (lib "28_Pins_Project_V1I1") (part "CG0603MLC-05E"))
    )
    (comp (ref "Z2")
      (value "CG0603MLC-05E")
      (footprint "R0603")
      (description "VARISTOR 0603")
      (fields (field (name "MANUFACTURER") "Bourns"))
      (libsource (lib "28_Pins_Project_V1I1") (part "CG0603MLC-05E"))
    )
  )
  (nets
    (net (code "1") (name "+3V3") (class "Default")
      (node (ref "C3") (pin "2") (pinfunction "2_2") (pintype "passive"))
      (node (ref "J11") (pin "1") (pinfunction "1_1") (pintype "passive"))
      (node (ref "J2") (pin "4") (pinfunction "4_4") (pintype "passive"))
      (node (ref "R15") (pin "2") (pinfunction "1_2") (pintype "passive"))
    )
    (net (code "2") (name "+5V") (class "Default")
      (node (ref "C1") (pin "2") (pinfunction "2_2") (pintype "passive"))
      (node (ref "C13") (pin "1") (pinfunction "1_1") (pintype "passive"))
      (node (ref "C15") (pin "2") (pinfunction "2_2") (pintype "passive"))
      (node (ref "C26") (pin "2") (pinfunction "2_2") (pintype "passive"))
      (node (ref "J1") (pin "1") (pinfunction "1_1") (pintype "passive"))
      (node (ref "J11") (pin "3") (pinfunction "3_3") (pintype "passive"))
      (node (ref "J2") (pin "5") (pinfunction "5_5") (pintype "passive"))
      (node (ref "L1") (pin "4") (pinfunction "4_4") (pintype "passive"))
      (node (ref "U1") (pin "31") (pinfunction "UVCC_31") (pintype "passive"))
      (node (ref "U3") (pin "1") (pinfunction "SHDN_1") (pintype "passive"))
      (node (ref "U3") (pin "2") (pinfunction "IN_2") (pintype "passive"))
    )
    (net (code "3") (name "+5V{slash}3V3") (class "Default")
      (node (ref "C16") (pin "2") (pinfunction "2_2") (pintype "passive"))
      (node (ref "C2") (pin "2") (pinfunction "2_2") (pintype "passive"))
      (node (ref "C25") (pin "2") (pinfunction "2_2") (pintype "passive"))
      (node (ref "C27") (pin "2") (pinfunction "2_2") (pintype "passive"))
      (node (ref "C28") (pin "2") (pinfunction "2_2") (pintype "passive"))
      (node (ref "C29") (pin "2") (pinfunction "2_2") (pintype "passive"))
      (node (ref "C30") (pin "2") (pinfunction "2_2") (pintype "passive"))
      (node (ref "C4") (pin "2") (pinfunction "2_2") (pintype "passive"))
      (node (ref "C7") (pin "2") (pinfunction "2_2") (pintype "passive"))
      (node (ref "D5") (pin "1") (pinfunction "Cathode_1") (pintype "passive"))
      (node (ref "D6") (pin "1") (pinfunction "Cathode_1") (pintype "passive"))
      (node (ref "FB1") (pin "1") (pinfunction "1_1") (pintype "passive"))
      (node (ref "FB2") (pin "1") (pinfunction "1_1") (pintype "passive"))
      (node (ref "FB3") (pin "1") (pinfunction "1_1") (pintype "passive"))
      (node (ref "J11") (pin "2") (pinfunction "2_2") (pintype "passive"))
      (node (ref "J2") (pin "2") (pinfunction "2_2") (pintype "passive"))
      (node (ref "J6") (pin "2") (pinfunction "2_2") (pintype "passive"))
      (node (ref "J9") (pin "2") (pinfunction "2_2") (pintype "passive"))
      (node (ref "R1") (pin "2") (pinfunction "1_2") (pintype "passive"))
      (node (ref "R14") (pin "2") (pinfunction "1_2") (pintype "passive"))
      (node (ref "R16") (pin "2") (pinfunction "1_2") (pintype "passive"))
      (node (ref "R19") (pin "2") (pinfunction "1_2") (pintype "passive"))
      (node (ref "R2") (pin "2") (pinfunction "1_2") (pintype "passive"))
      (node (ref "R20") (pin "2") (pinfunction "1_2") (pintype "passive"))
      (node (ref "R21") (pin "2") (pinfunction "1_2") (pintype "passive"))
      (node (ref "R22") (pin "2") (pinfunction "1_2") (pintype "passive"))
      (node (ref "R23") (pin "2") (pinfunction "1_2") (pintype "passive"))
      (node (ref "R24") (pin "2") (pinfunction "1_2") (pintype "passive"))
      (node (ref "R6") (pin "1") (pinfunction "1_1") (pintype "passive"))
      (node (ref "R7") (pin "2") (pinfunction "1_2") (pintype "passive"))
      (node (ref "U3") (pin "4") (pinfunction "OUT_4") (pintype "passive"))
      (node (ref "U3") (pin "5") (pinfunction "SENSE_5") (pintype "passive"))
      (node (ref "U4") (pin "5") (pinfunction "5_5") (pintype "passive"))
      (node (ref "U5") (pin "5") (pinfunction "5_5") (pintype "passive"))
      (node (ref "U6") (pin "5") (pinfunction "5_5") (pintype "passive"))
      (node (ref "U7") (pin "5") (pinfunction "5_5") (pintype "passive"))
    )
    (net (code "4") (name "+AREF") (class "Default")
      (node (ref "C17") (pin "2") (pinfunction "2_2") (pintype "passive"))
      (node (ref "C22") (pin "2") (pinfunction "2_2") (pintype "passive"))
      (node (ref "J10") (pin "8") (pinfunction "8_8") (pintype "passive"))
      (node (ref "U2") (pin "21") (pinfunction "AREF_21") (pintype "passive"))
    )
    (net (code "5") (name "/+3V3_16U2_UCAP") (class "Default")
      (node (ref "C14") (pin "2") (pinfunction "2_2") (pintype "passive"))
      (node (ref "R8") (pin "2") (pinfunction "1_2") (pintype "passive"))
      (node (ref "U1") (pin "27") (pinfunction "UCAP_27") (pintype "passive"))
    )
    (net (code "6") (name "/+5V_USB") (class "Default")
      (node (ref "C12") (pin "1") (pinfunction "1_1") (pintype "passive"))
      (node (ref "J7") (pin "1") (pinfunction "1_1") (pintype "passive"))
      (node (ref "L1") (pin "3") (pinfunction "3_3") (pintype "passive"))
    )
    (net (code "7") (name "/+5V{slash}3V3_16U2") (class "Default")
      (node (ref "C10") (pin "2") (pinfunction "2_2") (pintype "passive"))
      (node (ref "C11") (pin "2") (pinfunction "2_2") (pintype "passive"))
      (node (ref "C9") (pin "2") (pinfunction "2_2") (pintype "passive"))
      (node (ref "FB1") (pin "2") (pinfunction "2_2") (pintype "passive"))
      (node (ref "R8") (pin "2") (pinfunction "1_2") (pintype "passive"))
      (node (ref "U1") (pin "32") (pinfunction "AVCC_32") (pintype "passive"))
      (node (ref "U1") (pin "4") (pinfunction "VCC_4") (pintype "passive"))
    )
    (net (code "8") (name "/5V{slash}3V3_328P_AVCC") (class "Default")
      (node (ref "C20") (pin "2") (pinfunction "2_2") (pintype "passive"))
      (node (ref "C21") (pin "2") (pinfunction "2_2") (pintype "passive"))
      (node (ref "FB2") (pin "2") (pinfunction "2_2") (pintype "passive"))
      (node (ref "U2") (pin "20") (pinfunction "AVCC_20") (pintype "passive"))
    )
    (net (code "9") (name "/5V{slash}3V3_328P_VCC") (class "Default")
      (node (ref "C23") (pin "2") (pinfunction "2_2") (pintype "passive"))
      (node (ref "C24") (pin "2") (pinfunction "2_2") (pintype "passive"))
      (node (ref "FB3") (pin "2") (pinfunction "2_2") (pintype "passive"))
      (node (ref "U2") (pin "7") (pinfunction "VCC_7") (pintype "passive"))
    )
    (net (code "10") (name "/16U2PROG_328P_RESETn") (class "Default")
      (node (ref "J5") (pin "2") (pinfunction "2_2") (pintype "passive"))
      (node (ref "R1") (pin "1") (pinfunction "1_1") (pintype "passive"))
      (node (ref "U1") (pin "13") (pinfunction "/_HWB_/_AIN6_/_T0_/_INT7)_PD7_13") (pintype "passive"))
    )
    (net (code "11") (name "/16U2_16MHZ_XTAL1") (class "Default")
      (node (ref "C8") (pin "2") (pinfunction "2_2") (pintype "passive"))
      (node (ref "R3") (pin "1") (pinfunction "1_1") (pintype "passive"))
      (node (ref "U1") (pin "1") (pinfunction "XTAL1_1") (pintype "passive"))
      (node (ref "Y1") (pin "1") (pinfunction "1_1") (pintype "passive"))
    )
    (net (code "12") (name "/16U2_16MHZ_XTAL2") (class "Default")
      (node (ref "C6") (pin "2") (pinfunction "2_2") (pintype "passive"))
      (node (ref "R3") (pin "2") (pinfunction "1_2") (pintype "passive"))
      (node (ref "U1") (pin "2") (pinfunction "(PC0)_XTAL2_2") (pintype "passive"))
    )
    (net (code "13") (name "/16U2_BUF_RESETn") (class "Default")
      (node (ref "C33") (pin "2") (pinfunction "2_2") (pintype "passive"))
      (node (ref "R28") (pin "2") (pinfunction "1_2") (pintype "passive"))
      (node (ref "U7") (pin "1") (pinfunction "1_1") (pintype "passive"))
      (node (ref "U7") (pin "2") (pinfunction "2_2") (pintype "passive"))
    )
    (net (code "14") (name "/16U2_HDR_RESETn") (class "Default")
      (node (ref "J6") (pin "5") (pinfunction "5_5") (pintype "passive"))
      (node (ref "J8") (pin "3") (pinfunction "3_3") (pintype "passive"))
    )
    (net (code "15") (name "/16U2_MISO") (class "Default")
      (node (ref "J6") (pin "1") (pinfunction "1_1") (pintype "passive"))
      (node (ref "U1") (pin "17") (pinfunction "PB3_(PDO_/_MISO_/_PCINT3)_17") (pintype "passive"))
    )
    (net (code "16") (name "/16U2_MOSI") (class "Default")
      (node (ref "J6") (pin "4") (pinfunction "4_4") (pintype "passive"))
      (node (ref "U1") (pin "16") (pinfunction "(PDI_/_MOSI_/_PCINT2)_PB2_16") (pintype "passive"))
    )
    (net (code "17") (name "/16U2_PB4") (class "Default")
      (node (ref "J4") (pin "1") (pinfunction "1_1") (pintype "passive"))
      (node (ref "J8") (pin "2") (pinfunction "2_2") (pintype "passive"))
      (node (ref "U1") (pin "18") (pinfunction "PB4_(T1_/_PCINT4)_18") (pintype "passive"))
    )
    (net (code "18") (name "/16U2_PB5") (class "Default")
      (node (ref "J4") (pin "3") (pinfunction "3_3") (pintype "passive"))
      (node (ref "U1") (pin "19") (pinfunction "PB5_(PCINT5)_19") (pintype "passive"))
    )
    (net (code "19") (name "/16U2_PB6") (class "Default")
      (node (ref "J4") (pin "2") (pinfunction "2_2") (pintype "passive"))
      (node (ref "U1") (pin "20") (pinfunction "PB6_(PCINT6)_20") (pintype "passive"))
    )
    (net (code "20") (name "/16U2_PB7") (class "Default")
      (node (ref "J4") (pin "4") (pinfunction "4_4") (pintype "passive"))
      (node (ref "U1") (pin "21") (pinfunction "PB7_(PCINT7_/_OC.0A_/_OC.1C)_21") (pintype "passive"))
    )
    (net (code "21") (name "/16U2_RESETn") (class "Default")
      (node (ref "J8") (pin "4") (pinfunction "4_4") (pintype "passive"))
      (node (ref "R2") (pin "1") (pinfunction "1_1") (pintype "passive"))
      (node (ref "U1") (pin "24") (pinfunction "Reset_(PC1_/_dW)_24") (pintype "passive"))
      (node (ref "U7") (pin "4") (pinfunction "4_4") (pintype "passive"))
    )
    (net (code "22") (name "/16U2_RXD") (class "Default")
      (node (ref "R11") (pin "1") (pinfunction "1_1") (pintype "passive"))
      (node (ref "U1") (pin "8") (pinfunction "(RXD1_/_AIN1_/_INT2)_PD2_8") (pintype "passive"))
    )
    (net (code "23") (name "/16U2_RX_LED") (class "Default")
      (node (ref "D2") (pin "1") (pinfunction "Cathode_1") (pintype "passive"))
      (node (ref "U1") (pin "10") (pinfunction "(INT5/_AIN3)_PD4_10") (pintype "passive"))
    )
    (net (code "24") (name "/16U2_SCLK") (class "Default")
      (node (ref "J6") (pin "3") (pinfunction "3_3") (pintype "passive"))
      (node (ref "R4") (pin "2") (pinfunction "1_2") (pintype "passive"))
    )
    (net (code "25") (name "/16U2_SCLK_R") (class "Default")
      (node (ref "R4") (pin "2") (pinfunction "1_2") (pintype "passive"))
      (node (ref "U1") (pin "15") (pinfunction "(SCLK_/_PCINT1)_PB1_15") (pintype "passive"))
    )
    (net (code "26") (name "/16U2_TXD") (class "Default")
      (node (ref "R9") (pin "1") (pinfunction "1_1") (pintype "passive"))
      (node (ref "U1") (pin "9") (pinfunction "(TXD1_/_INT3)_PD3_9") (pintype "passive"))
    )
    (net (code "27") (name "/16U2_TX_LED") (class "Default")
      (node (ref "D1") (pin "1") (pinfunction "Cathode_1") (pintype "passive"))
      (node (ref "U1") (pin "11") (pinfunction "(XCK_AIN4_/_PCINT12)_PD5_11") (pintype "passive"))
    )
    (net (code "28") (name "/328P RESETn") (class "Default")
      (node (ref "J2") (pin "3") (pinfunction "3_3") (pintype "passive"))
      (node (ref "J9") (pin "5") (pinfunction "5_5") (pintype "passive"))
    )
    (net (code "29") (name "/328P_16MHZ_XTAL1") (class "Default")
      (node (ref "C19") (pin "2") (pinfunction "2_2") (pintype "passive"))
      (node (ref "R18") (pin "1") (pinfunction "1_1") (pintype "passive"))
      (node (ref "U2") (pin "9") (pinfunction "(PCINT6/XTAL1/TOSC1)_PB6_9") (pintype "passive"))
    )
    (net (code "30") (name "/328P_16MHZ_XTAL2") (class "Default")
      (node (ref "C18") (pin "2") (pinfunction "2_2") (pintype "passive"))
      (node (ref "R18") (pin "2") (pinfunction "1_2") (pintype "passive"))
      (node (ref "U2") (pin "10") (pinfunction "(PCINT7/XTAL2/TOSC2)_PB7_10") (pintype "passive"))
    )
    (net (code "31") (name "/328P_AUTORESETn") (class "Default")
      (node (ref "C5") (pin "1") (pinfunction "1_1") (pintype "passive"))
      (node (ref "R23") (pin "1") (pinfunction "1_1") (pintype "passive"))
      (node (ref "U6") (pin "1") (pinfunction "1_1") (pintype "passive"))
    )
    (net (code "32") (name "/328P_BUF_RESETn") (class "Default")
      (node (ref "C32") (pin "2") (pinfunction "2_2") (pintype "passive"))
      (node (ref "R27") (pin "2") (pinfunction "1_2") (pintype "passive"))
      (node (ref "U6") (pin "2") (pinfunction "2_2") (pintype "passive"))
    )
    (net (code "33") (name "/328P_RESETn") (class "Default")
      (node (ref "J8") (pin "1") (pinfunction "1_1") (pintype "passive"))
      (node (ref "R16") (pin "1") (pinfunction "1_1") (pintype "passive"))
      (node (ref "U2") (pin "1") (pinfunction "(PCINT14/RESET)_PC6_1") (pintype "passive"))
      (node (ref "U6") (pin "4") (pinfunction "4_4") (pintype "passive"))
    )
    (net (code "34") (name "/AD0") (class "Default")
      (node (ref "J12") (pin "1") (pinfunction "1_1") (pintype "passive"))
      (node (ref "U2") (pin "23") (pinfunction "PC0_(ADC0/PCINT8)_23") (pintype "passive"))
    )
    (net (code "35") (name "/AD1") (class "Default")
      (node (ref "J12") (pin "2") (pinfunction "2_2") (pintype "passive"))
      (node (ref "U2") (pin "24") (pinfunction "PC1_(ADC1/PCINT9)_24") (pintype "passive"))
    )
    (net (code "36") (name "/AD2") (class "Default")
      (node (ref "J12") (pin "3") (pinfunction "3_3") (pintype "passive"))
      (node (ref "U2") (pin "25") (pinfunction "PC2_(ADC2/PCINT10)_25") (pintype "passive"))
    )
    (net (code "37") (name "/AD3") (class "Default")
      (node (ref "J12") (pin "4") (pinfunction "4_4") (pintype "passive"))
      (node (ref "U2") (pin "26") (pinfunction "PC3_(ADC3/PCINT11)_26") (pintype "passive"))
    )
    (net (code "38") (name "/AD4{slash}SDA") (class "Default")
      (node (ref "J10") (pin "9") (pinfunction "9_9") (pintype "passive"))
      (node (ref "J12") (pin "5") (pinfunction "5_5") (pintype "passive"))
      (node (ref "U2") (pin "27") (pinfunction "PC4_(ADC4/SDA/PCINT12)_27") (pintype "passive"))
    )
    (net (code "39") (name "/AD5{slash}SCL") (class "Default")
      (node (ref "J10") (pin "10") (pinfunction "10_10") (pintype "passive"))
      (node (ref "J12") (pin "6") (pinfunction "6_6") (pintype "passive"))
      (node (ref "U2") (pin "28") (pinfunction "PC5_(ADC5/SCL/PCINT13)_28") (pintype "passive"))
    )
    (net (code "40") (name "/BUTTON_RESETn") (class "Default")
      (node (ref "D5") (pin "2") (pinfunction "Anode_2") (pintype "passive"))
      (node (ref "R22") (pin "1") (pinfunction "1_1") (pintype "passive"))
      (node (ref "R27") (pin "2") (pinfunction "1_2") (pintype "passive"))
      (node (ref "SW2") (pin "1") (pinfunction "1_1") (pintype "passive"))
      (node (ref "SW2") (pin "2") (pinfunction "2_2") (pintype "passive"))
    )
    (net (code "41") (name "/CON_USB_N") (class "Default")
      (node (ref "J7") (pin "2") (pinfunction "2_2") (pintype "passive"))
      (node (ref "R10") (pin "2") (pinfunction "1_2") (pintype "passive"))
      (node (ref "Z1") (pin "2") (pinfunction "2_2") (pintype "passive"))
    )
    (net (code "42") (name "/CON_USB_P") (class "Default")
      (node (ref "J7") (pin "3") (pinfunction "3_3") (pintype "passive"))
      (node (ref "R13") (pin "2") (pinfunction "1_2") (pintype "passive"))
      (node (ref "Z2") (pin "2") (pinfunction "2_2") (pintype "passive"))
    )
    (net (code "43") (name "/IO0") (class "Default")
      (node (ref "J13") (pin "1") (pinfunction "1_1") (pintype "passive"))
      (node (ref "R9") (pin "2") (pinfunction "1_2") (pintype "passive"))
      (node (ref "U2") (pin "2") (pinfunction "(PCINT16/RXD)_PD0_2") (pintype "passive"))
    )
    (net (code "44") (name "/IO1") (class "Default")
      (node (ref "J13") (pin "2") (pinfunction "2_2") (pintype "passive"))
      (node (ref "R11") (pin "2") (pinfunction "1_2") (pintype "passive"))
      (node (ref "U2") (pin "3") (pinfunction "(PCINT17/TXD)_PD1_3") (pintype "passive"))
    )
    (net (code "45") (name "/IO2") (class "Default")
      (node (ref "J13") (pin "3") (pinfunction "3_3") (pintype "passive"))
      (node (ref "U2") (pin "4") (pinfunction "(PCINT18/INT0)_PD2_4") (pintype "passive"))
    )
    (net (code "46") (name "/IO3") (class "Default")
      (node (ref "J13") (pin "4") (pinfunction "4_4") (pintype "passive"))
      (node (ref "U2") (pin "5") (pinfunction "(PCINT19/OC2B/INT1)_PD3_5") (pintype "passive"))
    )
    (net (code "47") (name "/IO4") (class "Default")
      (node (ref "J13") (pin "5") (pinfunction "5_5") (pintype "passive"))
      (node (ref "U2") (pin "6") (pinfunction "(PCINT20/XCK/T0)_PD4_6") (pintype "passive"))
    )
    (net (code "48") (name "/IO5") (class "Default")
      (node (ref "J13") (pin "6") (pinfunction "6_6") (pintype "passive"))
      (node (ref "U2") (pin "11") (pinfunction "(PCINT21/OC0B/T1)_PD5_11") (pintype "passive"))
    )
    (net (code "49") (name "/IO6") (class "Default")
      (node (ref "J13") (pin "7") (pinfunction "7_7") (pintype "passive"))
      (node (ref "U2") (pin "12") (pinfunction "(PCINT22/OC0A/AIN0)_PD6_12") (pintype "passive"))
    )
    (net (code "50") (name "/IO7") (class "Default")
      (node (ref "J13") (pin "8") (pinfunction "8_8") (pintype "passive"))
      (node (ref "U2") (pin "13") (pinfunction "(PCINT23/AIN1)_PD7_13") (pintype "passive"))
    )
    (net (code "51") (name "/IO8") (class "Default")
      (node (ref "J10") (pin "1") (pinfunction "1_1") (pintype "passive"))
      (node (ref "R25") (pin "2") (pinfunction "1_2") (pintype "passive"))
      (node (ref "U2") (pin "14") (pinfunction "(PCINT0/CLKO/ICP1)_PB0_14") (pintype "passive"))
    )
    (net (code "52") (name "/IO9") (class "Default")
      (node (ref "J10") (pin "2") (pinfunction "2_2") (pintype "passive"))
      (node (ref "U2") (pin "15") (pinfunction "PB1_(OC1A/PCINT1)_15") (pintype "passive"))
    )
    (net (code "53") (name "/MISO") (class "Default")
      (node (ref "J10") (pin "5") (pinfunction "5_5") (pintype "passive"))
      (node (ref "J9") (pin "1") (pinfunction "1_1") (pintype "passive"))
      (node (ref "U2") (pin "18") (pinfunction "PB4_(MISO/PCINT4)_18") (pintype "passive"))
    )
    (net (code "54") (name "/MOSI") (class "Default")
      (node (ref "J10") (pin "4") (pinfunction "4_4") (pintype "passive"))
      (node (ref "J9") (pin "4") (pinfunction "4_4") (pintype "passive"))
      (node (ref "U2") (pin "17") (pinfunction "PB3_(MOSI/OC2A/PCINT3)_17") (pintype "passive"))
    )
    (net (code "55") (name "/SCK") (class "Default")
      (node (ref "J10") (pin "6") (pinfunction "6_6") (pintype "passive"))
      (node (ref "J9") (pin "3") (pinfunction "3_3") (pintype "passive"))
      (node (ref "R17") (pin "2") (pinfunction "1_2") (pintype "passive"))
      (node (ref "U4") (pin "1") (pinfunction "1_1") (pintype "passive"))
      (node (ref "U4") (pin "2") (pinfunction "2_2") (pintype "passive"))
    )
    (net (code "56") (name "/SCK_R") (class "Default")
      (node (ref "R17") (pin "2") (pinfunction "1_2") (pintype "passive"))
      (node (ref "U2") (pin "19") (pinfunction "PB5_(SCK/PCINT5)_19") (pintype "passive"))
    )
    (net (code "57") (name "/SS") (class "Default")
      (node (ref "J10") (pin "3") (pinfunction "3_3") (pintype "passive"))
      (node (ref "U2") (pin "16") (pinfunction "PB2_(SS/OC1B/PCINT2)_16") (pintype "passive"))
    )
    (net (code "58") (name "/USB_N") (class "Default")
      (node (ref "R10") (pin "2") (pinfunction "1_2") (pintype "passive"))
      (node (ref "U1") (pin "30") (pinfunction "D-_30") (pintype "passive"))
    )
    (net (code "59") (name "/USB_P") (class "Default")
      (node (ref "R13") (pin "2") (pinfunction "1_2") (pintype "passive"))
      (node (ref "U1") (pin "29") (pinfunction "D+_29") (pintype "passive"))
    )
    (net (code "60") (name "/USER_BUTTON") (class "Default")
      (node (ref "R21") (pin "1") (pinfunction "1_1") (pintype "passive"))
      (node (ref "R26") (pin "2") (pinfunction "1_2") (pintype "passive"))
      (node (ref "SW1") (pin "1") (pinfunction "1_1") (pintype "passive"))
      (node (ref "SW1") (pin "2") (pinfunction "2_2") (pintype "passive"))
    )
    (net (code "61") (name "/USER_BUTTON_BUF") (class "Default")
      (node (ref "C31") (pin "2") (pinfunction "2_2") (pintype "passive"))
      (node (ref "R26") (pin "2") (pinfunction "1_2") (pintype "passive"))
      (node (ref "U5") (pin "1") (pinfunction "1_1") (pintype "passive"))
      (node (ref "U5") (pin "2") (pinfunction "2_2") (pintype "passive"))
    )
    (net (code "62") (name "GND") (class "Default")
      (node (ref "C1") (pin "1") (pinfunction "1_1") (pintype "passive"))
      (node (ref "C10") (pin "1") (pinfunction "1_1") (pintype "passive"))
      (node (ref "C11") (pin "1") (pinfunction "1_1") (pintype "passive"))
      (node (ref "C12") (pin "2") (pinfunction "2_2") (pintype "passive"))
      (node (ref "C13") (pin "2") (pinfunction "2_2") (pintype "passive"))
      (node (ref "C14") (pin "1") (pinfunction "1_1") (pintype "passive"))
      (node (ref "C15") (pin "1") (pinfunction "1_1") (pintype "passive"))
      (node (ref "C16") (pin "1") (pinfunction "1_1") (pintype "passive"))
      (node (ref "C17") (pin "1") (pinfunction "1_1") (pintype "passive"))
      (node (ref "C18") (pin "1") (pinfunction "1_1") (pintype "passive"))
      (node (ref "C19") (pin "1") (pinfunction "1_1") (pintype "passive"))
      (node (ref "C2") (pin "1") (pinfunction "1_1") (pintype "passive"))
      (node (ref "C20") (pin "1") (pinfunction "1_1") (pintype "passive"))
      (node (ref "C21") (pin "1") (pinfunction "1_1") (pintype "passive"))
      (node (ref "C22") (pin "1") (pinfunction "1_1") (pintype "passive"))
      (node (ref "C23") (pin "1") (pinfunction "1_1") (pintype "passive"))
      (node (ref "C24") (pin "1") (pinfunction "1_1") (pintype "passive"))
      (node (ref "C25") (pin "1") (pinfunction "1_1") (pintype "passive"))
      (node (ref "C26") (pin "1") (pinfunction "1_1") (pintype "passive"))
      (node (ref "C27") (pin "1") (pinfunction "1_1") (pintype "passive"))
      (node (ref "C28") (pin "1") (pinfunction "1_1") (pintype "passive"))
      (node (ref "C29") (pin "1") (pinfunction "1_1") (pintype "passive"))
      (node (ref "C3") (pin "1") (pinfunction "1_1") (pintype "passive"))
      (node (ref "C30") (pin "1") (pinfunction "1_1") (pintype "passive"))
      (node (ref "C31") (pin "1") (pinfunction "1_1") (pintype "passive"))
      (node (ref "C32") (pin "1") (pinfunction "1_1") (pintype "passive"))
      (node (ref "C33") (pin "1") (pinfunction "1_1") (pintype "passive"))
      (node (ref "C4") (pin "1") (pinfunction "1_1") (pintype "passive"))
      (node (ref "C6") (pin "1") (pinfunction "1_1") (pintype "passive"))
      (node (ref "C7") (pin "1") (pinfunction "1_1") (pintype "passive"))
      (node (ref "C8") (pin "1") (pinfunction "1_1") (pintype "passive"))
      (node (ref "C9") (pin "1") (pinfunction "1_1") (pintype "passive"))
      (node (ref "D3") (pin "1") (pinfunction "Cathode_1") (pintype "passive"))
      (node (ref "J10") (pin "7") (pinfunction "7_7") (pintype "passive"))
      (node (ref "J2") (pin "6") (pinfunction "6_6") (pintype "passive"))
      (node (ref "J2") (pin "7") (pinfunction "7_7") (pintype "passive"))
      (node (ref "J3") (pin "1") (pinfunction "1_1") (pintype "passive"))
      (node (ref "J6") (pin "6") (pinfunction "6_6") (pintype "passive"))
      (node (ref "J7") (pin "10") (pinfunction "10_10") (pintype "passive"))
      (node (ref "J7") (pin "11") (pinfunction "11_11") (pintype "passive"))
      (node (ref "J7") (pin "5") (pinfunction "5_5") (pintype "passive"))
      (node (ref "J7") (pin "6") (pinfunction "6_6") (pintype "passive"))
      (node (ref "J7") (pin "7") (pinfunction "7_7") (pintype "passive"))
      (node (ref "J7") (pin "8") (pinfunction "8_8") (pintype "passive"))
      (node (ref "J7") (pin "9") (pinfunction "9_9") (pintype "passive"))
      (node (ref "J9") (pin "6") (pinfunction "6_6") (pintype "passive"))
      (node (ref "MH1") (pin "1") (pinfunction "1_1") (pintype "passive"))
      (node (ref "MH2") (pin "1") (pinfunction "1_1") (pintype "passive"))
      (node (ref "MH3") (pin "1") (pinfunction "1_1") (pintype "passive"))
      (node (ref "R12") (pin "2") (pinfunction "1_2") (pintype "passive"))
      (node (ref "R5") (pin "1") (pinfunction "1_1") (pintype "passive"))
      (node (ref "SW1") (pin "3") (pinfunction "3_3") (pintype "passive"))
      (node (ref "SW1") (pin "4") (pinfunction "4_4") (pintype "passive"))
      (node (ref "SW2") (pin "3") (pinfunction "3_3") (pintype "passive"))
      (node (ref "SW2") (pin "4") (pinfunction "4_4") (pintype "passive"))
      (node (ref "U1") (pin "28") (pinfunction "UGND_28") (pintype "passive"))
      (node (ref "U1") (pin "3") (pinfunction "GND_3") (pintype "passive"))
      (node (ref "U2") (pin "22") (pinfunction "GND_22") (pintype "passive"))
      (node (ref "U2") (pin "8") (pinfunction "GND_8") (pintype "passive"))
      (node (ref "U3") (pin "3") (pinfunction "GND_3") (pintype "passive"))
      (node (ref "U3") (pin "6") (pinfunction "EPAD_6") (pintype "passive"))
      (node (ref "U4") (pin "3") (pinfunction "3_3") (pintype "passive"))
      (node (ref "U5") (pin "3") (pinfunction "3_3") (pintype "passive"))
      (node (ref "U6") (pin "3") (pinfunction "3_3") (pintype "passive"))
      (node (ref "U7") (pin "3") (pinfunction "3_3") (pintype "passive"))
      (node (ref "Z1") (pin "1") (pinfunction "1_1") (pintype "passive"))
      (node (ref "Z2") (pin "1") (pinfunction "1_1") (pintype "passive"))
    )
    (net (code "63") (name "Net-(C5-Pad2)") (class "Default")
      (node (ref "C5") (pin "2") (pinfunction "2_2") (pintype "passive"))
      (node (ref "J5") (pin "1") (pinfunction "1_1") (pintype "passive"))
    )
    (net (code "64") (name "Net-(D1-Anode)") (class "Default")
      (node (ref "D1") (pin "2") (pinfunction "Anode_2") (pintype "passive"))
      (node (ref "R6") (pin "2") (pinfunction "1_2") (pintype "passive"))
    )
    (net (code "65") (name "Net-(D2-Anode)") (class "Default")
      (node (ref "D2") (pin "2") (pinfunction "Anode_2") (pintype "passive"))
      (node (ref "R7") (pin "1") (pinfunction "1_1") (pintype "passive"))
    )
    (net (code "66") (name "Net-(D3-Anode)") (class "Default")
      (node (ref "D3") (pin "2") (pinfunction "Anode_2") (pintype "passive"))
      (node (ref "R19") (pin "1") (pinfunction "1_1") (pintype "passive"))
    )
    (net (code "67") (name "Net-(D4-Anode)") (class "Default")
      (node (ref "D4") (pin "2") (pinfunction "Anode_2") (pintype "passive"))
      (node (ref "R20") (pin "1") (pinfunction "1_1") (pintype "passive"))
    )
    (net (code "68") (name "Net-(D4-Cathode)") (class "Default")
      (node (ref "D4") (pin "1") (pinfunction "Cathode_1") (pintype "passive"))
      (node (ref "U4") (pin "4") (pinfunction "4_4") (pintype "passive"))
    )
    (net (code "69") (name "Net-(D6-Anode)") (class "Default")
      (node (ref "D6") (pin "2") (pinfunction "Anode_2") (pintype "passive"))
      (node (ref "R24") (pin "1") (pinfunction "1_1") (pintype "passive"))
      (node (ref "R28") (pin "2") (pinfunction "1_2") (pintype "passive"))
    )
    (net (code "70") (name "Net-(J5-Pad3)") (class "Default")
      (node (ref "J5") (pin "3") (pinfunction "3_3") (pintype "passive"))
      (node (ref "R5") (pin "2") (pinfunction "1_2") (pintype "passive"))
    )
    (net (code "71") (name "Net-(R12-1)") (class "Default")
      (node (ref "J7") (pin "4") (pinfunction "4_4") (pintype "passive"))
      (node (ref "R12") (pin "2") (pinfunction "1_2") (pintype "passive"))
    )
    (net (code "72") (name "Net-(R25-Pad1)") (class "Default")
      (node (ref "R25") (pin "1") (pinfunction "1_1") (pintype "passive"))
      (node (ref "U5") (pin "4") (pinfunction "4_4") (pintype "passive"))
    )
    (net (code "73") (name "unconnected-(J2-Pad1)") (class "Default")
      (node (ref "J2") (pin "1") (pinfunction "1_1") (pintype "passive+no_connect"))
    )
    (net (code "74") (name "unconnected-(J2-Pad8)") (class "Default")
      (node (ref "J2") (pin "8") (pinfunction "8_8") (pintype "passive+no_connect"))
    )
    (net (code "75") (name "unconnected-(MH4-Pad1)") (class "Default")
      (node (ref "MH4") (pin "1") (pinfunction "1_1") (pintype "passive+no_connect"))
    )
    (net (code "76") (name "unconnected-(R14-1-Pad2)") (class "Default")
      (node (ref "R14") (pin "2") (pinfunction "1_2") (pintype "passive"))
    )
    (net (code "77") (name "unconnected-(R15-1-Pad2)") (class "Default")
      (node (ref "R15") (pin "2") (pinfunction "1_2") (pintype "passive"))
    )
    (net (code "78") (name "unconnected-(U1-(AIN0_{slash}_INT1)_PD1-Pad7)") (class "Default")
      (node (ref "U1") (pin "7") (pinfunction "(AIN0_/_INT1)_PD1_7") (pintype "passive+no_connect"))
    )
    (net (code "79") (name "unconnected-(U1-(OC.0B_{slash}_INT0)_PD0-Pad6)") (class "Default")
      (node (ref "U1") (pin "6") (pinfunction "(OC.0B_/_INT0)_PD0_6") (pintype "passive+no_connect"))
    )
    (net (code "80") (name "unconnected-(U1-(PCINT11_{slash}AIN2_)_PC2-Pad5)") (class "Default")
      (node (ref "U1") (pin "5") (pinfunction "(PCINT11_/AIN2_)_PC2_5") (pintype "passive+no_connect"))
    )
    (net (code "81") (name "unconnected-(U1-(RTS_{slash}_AIN5_{slash}_INT6)_PD6-Pad12)") (class "Default")
      (node (ref "U1") (pin "12") (pinfunction "(RTS_/_AIN5_/_INT6)_PD6_12") (pintype "passive+no_connect"))
    )
    (net (code "82") (name "unconnected-(U1-(SS_{slash}_PCINT0)_PB0-Pad14)") (class "Default")
      (node (ref "U1") (pin "14") (pinfunction "(SS_/_PCINT0)_PB0_14") (pintype "passive+no_connect"))
    )
    (net (code "83") (name "unconnected-(U1-PC4_(PCINT10)-Pad26)") (class "Default")
      (node (ref "U1") (pin "26") (pinfunction "PC4_(PCINT10)_26") (pintype "passive+no_connect"))
    )
    (net (code "84") (name "unconnected-(U1-PC5_(_PCINT9{slash}_OC.1B)-Pad25)") (class "Default")
      (node (ref "U1") (pin "25") (pinfunction "PC5_(_PCINT9/_OC.1B)_25") (pintype "passive+no_connect"))
    )
    (net (code "85") (name "unconnected-(U1-PC6_(OC.1A_{slash}_PCINT8)-Pad23)") (class "Default")
      (node (ref "U1") (pin "23") (pinfunction "PC6_(OC.1A_/_PCINT8)_23") (pintype "passive+no_connect"))
    )
    (net (code "86") (name "unconnected-(U1-PC7_(INT4_{slash}_ICP1_{slash}_CLKO)-Pad22)") (class "Default")
      (node (ref "U1") (pin "22") (pinfunction "PC7_(INT4_/_ICP1_/_CLKO)_22") (pintype "passive+no_connect"))
    )
    (net (code "87") (name "unconnected-(Y1-Pad2)") (class "Default")
      (node (ref "Y1") (pin "2") (pinfunction "2_2") (pintype "passive"))
    )
    (net (code "88") (name "unconnected-(Y2-Pad1)") (class "Default")
      (node (ref "Y2") (pin "1") (pinfunction "1_1") (pintype "passive"))
    )
    (net (code "89") (name "unconnected-(Y2-Pad2)") (class "Default")
      (node (ref "Y2") (pin "2") (pinfunction "2_2") (pintype "passive"))
    )
  )
)
